# CAN.net
KiCad netlist of a schematic drawn in Altium Designer
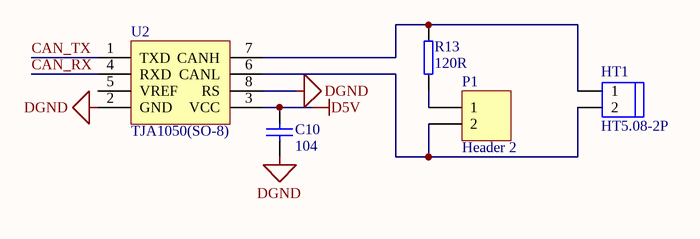
[diagram p0: CAN.SchDoc]

(export (version "E")
  (design (tool "Eeschema 10.0.6"))
  (components
    (comp (ref "C10")
      (value "104")
      (footprint "0805C")
      (description "贴片电容")
      (libsource (lib "常用元件") (part "Cap"))
    )
    (comp (ref "HT1")
      (value "HT5.08-2P")
      (footprint "HEAD2-5.08")
      (description "5.08蓝色接口座子")
      (libsource (lib "接口") (part "HT5.08-2P"))
    )
    (comp (ref "P1")
      (value "Header 2")
      (footprint "HDR1X2")
      (description "Header, 2-Pin")
      (fields (field (name "PUBLISHER") "Altium Limited"))
      (libsource (lib "Miscellaneous Connectors") (part "Header 2"))
    )
    (comp (ref "R13") (value "120R") (footprint "2512R") (libsource (lib "常用元件") (part "RES-10K")))
    (comp (ref "U2")
      (value "TJA1050(SO-8)")
      (description "CAN芯片")
      (libsource (lib "常用元件") (part "TJA1050(SO-8)"))
    )
  )
  (nets
    (net (code "1") (name "/CAN_RX") (class "Default")
      (node (ref "U2") (pin "4") (pinfunction "RXD_4") (pintype "passive"))
    )
    (net (code "2") (name "/CAN_TX") (class "Default")
      (node (ref "U2") (pin "1") (pinfunction "TXD_1") (pintype "passive"))
    )
    (net (code "3") (name "D5V") (class "Default")
      (node (ref "C10") (pin "2") (pinfunction "2_2") (pintype "passive"))
      (node (ref "U2") (pin "3") (pinfunction "VCC_3") (pintype "passive"))
    )
    (net (code "4") (name "DGND") (class "Default")
      (node (ref "C10") (pin "1") (pinfunction "1_1") (pintype "passive"))
      (node (ref "U2") (pin "2") (pinfunction "GND_2") (pintype "passive"))
      (node (ref "U2") (pin "8") (pinfunction "RS_8") (pintype "passive"))
    )
    (net (code "5") (name "Net-(P1-Pad1)") (class "Default")
      (node (ref "P1") (pin "1") (pinfunction "1_1") (pintype "passive"))
      (node (ref "R13") (pin "1") (pinfunction "1_1") (pintype "passive"))
    )
    (net (code "6") (name "Net-(U2-CANH)") (class "Default")
      (node (ref "HT1") (pin "1") (pinfunction "1_1") (pintype "passive"))
      (node (ref "R13") (pin "2") (pinfunction "2_2") (pintype "passive"))
      (node (ref "U2") (pin "7") (pinfunction "CANH_7") (pintype "passive"))
    )
    (net (code "7") (name "Net-(U2-CANL)") (class "Default")
      (node (ref "HT1") (pin "2") (pinfunction "2_2") (pintype "passive"))
      (node (ref "P1") (pin "2") (pinfunction "2_2") (pintype "passive"))
      (node (ref "U2") (pin "6") (pinfunction "CANL_6") (pintype "passive"))
    )
    (net (code "8") (name "unconnected-(U2-VREF-Pad5)") (class "Default")
      (node (ref "U2") (pin "5") (pinfunction "VREF_5") (pintype "passive"))
    )
  )
)
